# PDM-S01-V00-BatteryProtection.net
KiCad netlist of a schematic drawn in Altium Designer
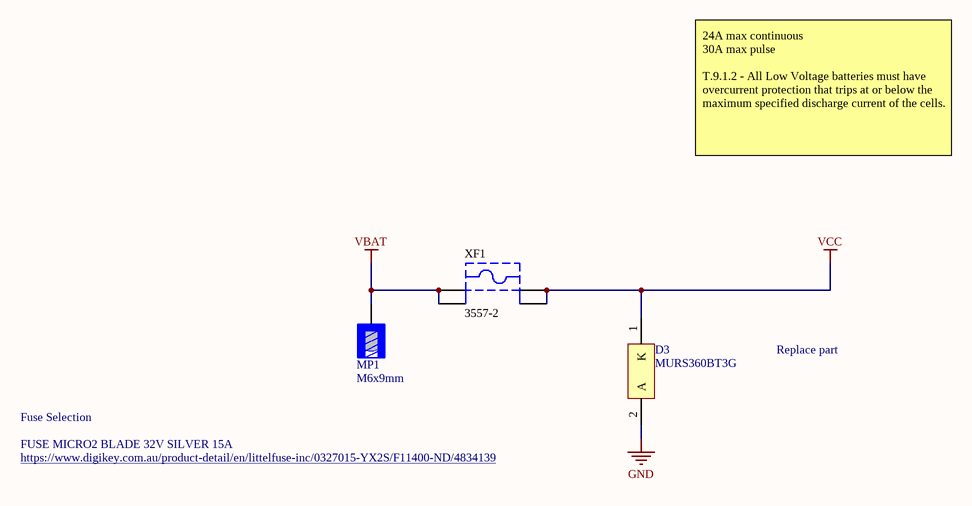
[diagram p0: PDM-S01-V00-BatteryProtection.SchDoc]

(export (version "E")
  (design (tool "Eeschema 10.0.6"))
  (components
    (comp (ref "D3")
      (value "MURS360BT3G")
      (footprint "ONSC-SMB-2-403A-03_V")
      (description "Surface Mount Ultrafast Power Rectifier, 2-Pin SMB, Pb-Free, Tape and Reel")
      (fields (field (name "MANUFACTURER") "On Semiconductor"))
      (libsource (lib "Altium Content Vault") (part "ONSC-D-K1A2-2_A"))
    )
    (comp (ref "MP1")
      (value "M6x9mm")
      (footprint "7461084_for chemical surfaces")
      (description "WP-BUTR Press-Fit with Internal thread, two rows, 10x10mm, 8 pins, M6x9mm, 160A")
      (fields (field (name "PART NUMBER") "7461084") (field (name "PUBLISHER") "Wurth Elektronik"))
      (libsource (lib "7461084_Altium_WP-BUTR_rev19a") (part "7461084"))
    )
    (comp (ref "XF1")
      (value "3557-2")
      (footprint "KSTN-3557-2")
      (description "FUSE HOLDER, PCB MOUNT, 500VAC, 20A, ROHS")
      (fields (field (name "VOLTAGE") "500V") (field (name "MANUFACTURER") "Keystone-Electronics"))
      (libsource (lib "Altium Content Vault") (part "FUSE_HOLDER-4"))
    )
  )
  (nets
    (net (code "1") (name "GND") (class "Default")
      (node (ref "D3") (pin "2") (pinfunction "A_2") (pintype "passive"))
    )
    (net (code "2") (name "VBAT") (class "Default")
      (node (ref "MP1") (pin "1") (pinfunction "1_1") (pintype "passive"))
      (node (ref "XF1") (pin "1") (pinfunction "1_1") (pintype "passive"))
      (node (ref "XF1") (pin "2") (pinfunction "2_2") (pintype "passive"))
    )
    (net (code "3") (name "VCC") (class "Default")
      (node (ref "D3") (pin "1") (pinfunction "K_1") (pintype "passive"))
      (node (ref "XF1") (pin "3") (pinfunction "3_3") (pintype "passive"))
      (node (ref "XF1") (pin "4") (pinfunction "4_4") (pintype "passive"))
    )
  )
)
